# PLA2216.net
KiCad netlist of a schematic drawn in Altium Designer
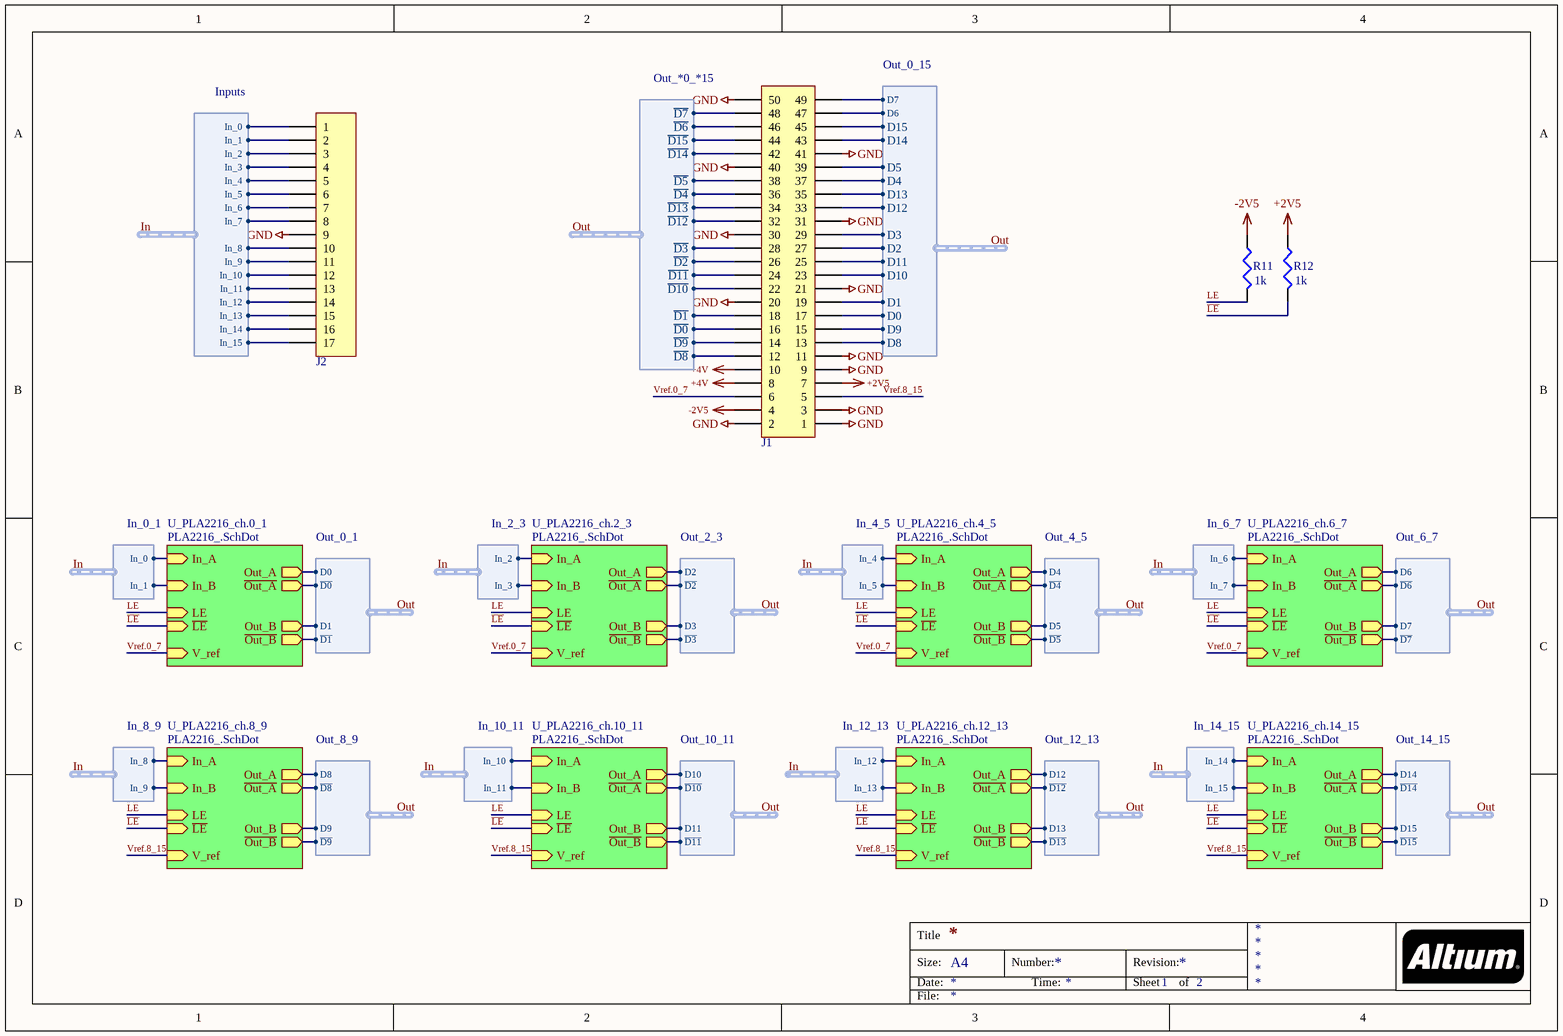
[diagram p0: PLA2216_.SchDoc]

(export (version "E")
  (design (tool "Eeschema 10.0.6"))
  (components
    (comp (ref "J1")
      (value "Header 25X2")
      (footprint "HEADER_25X2")
      (description "50 Position Total Dual Row 2.54 mm Pitch Straight Male Shrouded Box Header")
      (fields
        (field (name "MANUFACTURER") "Sullins")
        (field (name "MANUFACTURER PART NUMBER") "SBH11-PBPC-D25-ST-BK")
      )
      (libsource (lib "PLA2216_sonda") (part "SBH11-PBPC-D25-ST-BK"))
    )
    (comp (ref "J2")
      (value "Header 17X1vf")
      (footprint "HEADER_17")
      (description "Conn Unshrouded Header HDR 17 POS 2.54mm Solder RA Thru-Hole")
      (fields
        (field (name "MANUFACTURER") "Adam Equipment")
        (field (name "MANUFACTURER PART NUMBER") "PH1RB-17-UA")
      )
      (libsource (lib "PLA2216_sonda") (part "PH1RB-17-UA"))
    )
    (comp (ref "R11")
      (value "1k")
      (footprint "R0402")
      (description "Resistor Thick Film 0805 1k Ohm 1% 1/8 Watt ±100ppm °C Surface Mount Paper Tape On Plastic Reel")
      (fields (field (name "TOLERANCE") "1%") (field (name "MANUFACTURER") "Bourns"))
      (libsource (lib "PLA2216_sonda") (part "CR0805-FX-1001ELF"))
    )
    (comp (ref "R12")
      (value "1k")
      (footprint "R0402")
      (description "Resistor Thick Film 0805 1k Ohm 1% 1/8 Watt ±100ppm °C Surface Mount Paper Tape On Plastic Reel")
      (fields (field (name "TOLERANCE") "1%") (field (name "MANUFACTURER") "Bourns"))
      (libsource (lib "PLA2216_sonda") (part "CR0805-FX-1001ELF"))
    )
  )
  (nets
    (net (code "20") (name "+2V5") (class "Default")
      (node (ref "J1") (pin "7") (pinfunction "7_7") (pintype "passive"))
      (node (ref "R12") (pin "1") (pinfunction "1_1") (pintype "passive"))
    )
    (net (code "21") (name "+4V") (class "Default")
      (node (ref "J1") (pin "10") (pinfunction "10_10") (pintype "passive"))
      (node (ref "J1") (pin "8") (pinfunction "8_8") (pintype "passive"))
    )
    (net (code "22") (name "-2V5") (class "Default")
      (node (ref "J1") (pin "4") (pinfunction "4_4") (pintype "passive"))
      (node (ref "R11") (pin "1") (pinfunction "1_1") (pintype "passive"))
    )
    (net (code "48") (name "/LE") (class "Default")
      (node (ref "R11") (pin "2") (pinfunction "2_2") (pintype "passive"))
    )
    (net (code "91") (name "/Vref.0_7") (class "Default")
      (node (ref "J1") (pin "6") (pinfunction "6_6") (pintype "passive"))
    )
    (net (code "92") (name "/Vref.8_15") (class "Default")
      (node (ref "J1") (pin "5") (pinfunction "5_5") (pintype "passive"))
    )
    (net (code "93") (name "/~{LE}") (class "Default")
      (node (ref "R12") (pin "2") (pinfunction "2_2") (pintype "passive"))
    )
    (net (code "94") (name "GND") (class "Default")
      (node (ref "J1") (pin "1") (pinfunction "1_1") (pintype "passive"))
      (node (ref "J1") (pin "11") (pinfunction "11_11") (pintype "passive"))
      (node (ref "J1") (pin "2") (pinfunction "2_2") (pintype "passive"))
      (node (ref "J1") (pin "20") (pinfunction "20_20") (pintype "passive"))
      (node (ref "J1") (pin "21") (pinfunction "21_21") (pintype "passive"))
      (node (ref "J1") (pin "3") (pinfunction "3_3") (pintype "passive"))
      (node (ref "J1") (pin "30") (pinfunction "30_30") (pintype "passive"))
      (node (ref "J1") (pin "31") (pinfunction "31_31") (pintype "passive"))
      (node (ref "J1") (pin "40") (pinfunction "40_40") (pintype "passive"))
      (node (ref "J1") (pin "41") (pinfunction "41_41") (pintype "passive"))
      (node (ref "J1") (pin "50") (pinfunction "50_50") (pintype "passive"))
      (node (ref "J1") (pin "9") (pinfunction "9_9") (pintype "passive"))
      (node (ref "J2") (pin "9") (pinfunction "9_9") (pintype "passive"))
    )
    (net (code "95") (name "unconnected-(J1-Pad12)") (class "Default")
      (node (ref "J1") (pin "12") (pinfunction "12_12") (pintype "passive"))
    )
    (net (code "96") (name "unconnected-(J1-Pad13)") (class "Default")
      (node (ref "J1") (pin "13") (pinfunction "13_13") (pintype "passive"))
    )
    (net (code "97") (name "unconnected-(J1-Pad14)") (class "Default")
      (node (ref "J1") (pin "14") (pinfunction "14_14") (pintype "passive"))
    )
    (net (code "98") (name "unconnected-(J1-Pad15)") (class "Default")
      (node (ref "J1") (pin "15") (pinfunction "15_15") (pintype "passive"))
    )
    (net (code "99") (name "unconnected-(J1-Pad16)") (class "Default")
      (node (ref "J1") (pin "16") (pinfunction "16_16") (pintype "passive"))
    )
    (net (code "100") (name "unconnected-(J1-Pad17)") (class "Default")
      (node (ref "J1") (pin "17") (pinfunction "17_17") (pintype "passive"))
    )
    (net (code "101") (name "unconnected-(J1-Pad18)") (class "Default")
      (node (ref "J1") (pin "18") (pinfunction "18_18") (pintype "passive"))
    )
    (net (code "102") (name "unconnected-(J1-Pad19)") (class "Default")
      (node (ref "J1") (pin "19") (pinfunction "19_19") (pintype "passive"))
    )
    (net (code "103") (name "unconnected-(J1-Pad22)") (class "Default")
      (node (ref "J1") (pin "22") (pinfunction "22_22") (pintype "passive"))
    )
    (net (code "104") (name "unconnected-(J1-Pad23)") (class "Default")
      (node (ref "J1") (pin "23") (pinfunction "23_23") (pintype "passive"))
    )
    (net (code "105") (name "unconnected-(J1-Pad24)") (class "Default")
      (node (ref "J1") (pin "24") (pinfunction "24_24") (pintype "passive"))
    )
    (net (code "106") (name "unconnected-(J1-Pad25)") (class "Default")
      (node (ref "J1") (pin "25") (pinfunction "25_25") (pintype "passive"))
    )
    (net (code "107") (name "unconnected-(J1-Pad26)") (class "Default")
      (node (ref "J1") (pin "26") (pinfunction "26_26") (pintype "passive"))
    )
    (net (code "108") (name "unconnected-(J1-Pad27)") (class "Default")
      (node (ref "J1") (pin "27") (pinfunction "27_27") (pintype "passive"))
    )
    (net (code "109") (name "unconnected-(J1-Pad28)") (class "Default")
      (node (ref "J1") (pin "28") (pinfunction "28_28") (pintype "passive"))
    )
    (net (code "110") (name "unconnected-(J1-Pad29)") (class "Default")
      (node (ref "J1") (pin "29") (pinfunction "29_29") (pintype "passive"))
    )
    (net (code "111") (name "unconnected-(J1-Pad32)") (class "Default")
      (node (ref "J1") (pin "32") (pinfunction "32_32") (pintype "passive"))
    )
    (net (code "112") (name "unconnected-(J1-Pad33)") (class "Default")
      (node (ref "J1") (pin "33") (pinfunction "33_33") (pintype "passive"))
    )
    (net (code "113") (name "unconnected-(J1-Pad34)") (class "Default")
      (node (ref "J1") (pin "34") (pinfunction "34_34") (pintype "passive"))
    )
    (net (code "114") (name "unconnected-(J1-Pad35)") (class "Default")
      (node (ref "J1") (pin "35") (pinfunction "35_35") (pintype "passive"))
    )
    (net (code "115") (name "unconnected-(J1-Pad36)") (class "Default")
      (node (ref "J1") (pin "36") (pinfunction "36_36") (pintype "passive"))
    )
    (net (code "116") (name "unconnected-(J1-Pad37)") (class "Default")
      (node (ref "J1") (pin "37") (pinfunction "37_37") (pintype "passive"))
    )
    (net (code "117") (name "unconnected-(J1-Pad38)") (class "Default")
      (node (ref "J1") (pin "38") (pinfunction "38_38") (pintype "passive"))
    )
    (net (code "118") (name "unconnected-(J1-Pad39)") (class "Default")
      (node (ref "J1") (pin "39") (pinfunction "39_39") (pintype "passive"))
    )
    (net (code "119") (name "unconnected-(J1-Pad42)") (class "Default")
      (node (ref "J1") (pin "42") (pinfunction "42_42") (pintype "passive"))
    )
    (net (code "120") (name "unconnected-(J1-Pad43)") (class "Default")
      (node (ref "J1") (pin "43") (pinfunction "43_43") (pintype "passive"))
    )
    (net (code "121") (name "unconnected-(J1-Pad44)") (class "Default")
      (node (ref "J1") (pin "44") (pinfunction "44_44") (pintype "passive"))
    )
    (net (code "122") (name "unconnected-(J1-Pad45)") (class "Default")
      (node (ref "J1") (pin "45") (pinfunction "45_45") (pintype "passive"))
    )
    (net (code "123") (name "unconnected-(J1-Pad46)") (class "Default")
      (node (ref "J1") (pin "46") (pinfunction "46_46") (pintype "passive"))
    )
    (net (code "124") (name "unconnected-(J1-Pad47)") (class "Default")
      (node (ref "J1") (pin "47") (pinfunction "47_47") (pintype "passive"))
    )
    (net (code "125") (name "unconnected-(J1-Pad48)") (class "Default")
      (node (ref "J1") (pin "48") (pinfunction "48_48") (pintype "passive"))
    )
    (net (code "126") (name "unconnected-(J1-Pad49)") (class "Default")
      (node (ref "J1") (pin "49") (pinfunction "49_49") (pintype "passive"))
    )
    (net (code "127") (name "unconnected-(J2-Pad1)") (class "Default")
      (node (ref "J2") (pin "1") (pinfunction "1_1") (pintype "passive"))
    )
    (net (code "128") (name "unconnected-(J2-Pad2)") (class "Default")
      (node (ref "J2") (pin "2") (pinfunction "2_2") (pintype "passive"))
    )
    (net (code "129") (name "unconnected-(J2-Pad3)") (class "Default")
      (node (ref "J2") (pin "3") (pinfunction "3_3") (pintype "passive"))
    )
    (net (code "130") (name "unconnected-(J2-Pad4)") (class "Default")
      (node (ref "J2") (pin "4") (pinfunction "4_4") (pintype "passive"))
    )
    (net (code "131") (name "unconnected-(J2-Pad5)") (class "Default")
      (node (ref "J2") (pin "5") (pinfunction "5_5") (pintype "passive"))
    )
    (net (code "132") (name "unconnected-(J2-Pad6)") (class "Default")
      (node (ref "J2") (pin "6") (pinfunction "6_6") (pintype "passive"))
    )
    (net (code "133") (name "unconnected-(J2-Pad7)") (class "Default")
      (node (ref "J2") (pin "7") (pinfunction "7_7") (pintype "passive"))
    )
    (net (code "134") (name "unconnected-(J2-Pad8)") (class "Default")
      (node (ref "J2") (pin "8") (pinfunction "8_8") (pintype "passive"))
    )
    (net (code "135") (name "unconnected-(J2-Pad10)") (class "Default")
      (node (ref "J2") (pin "10") (pinfunction "10_10") (pintype "passive"))
    )
    (net (code "136") (name "unconnected-(J2-Pad11)") (class "Default")
      (node (ref "J2") (pin "11") (pinfunction "11_11") (pintype "passive"))
    )
    (net (code "137") (name "unconnected-(J2-Pad12)") (class "Default")
      (node (ref "J2") (pin "12") (pinfunction "12_12") (pintype "passive"))
    )
    (net (code "138") (name "unconnected-(J2-Pad13)") (class "Default")
      (node (ref "J2") (pin "13") (pinfunction "13_13") (pintype "passive"))
    )
    (net (code "139") (name "unconnected-(J2-Pad14)") (class "Default")
      (node (ref "J2") (pin "14") (pinfunction "14_14") (pintype "passive"))
    )
    (net (code "140") (name "unconnected-(J2-Pad15)") (class "Default")
      (node (ref "J2") (pin "15") (pinfunction "15_15") (pintype "passive"))
    )
    (net (code "141") (name "unconnected-(J2-Pad16)") (class "Default")
      (node (ref "J2") (pin "16") (pinfunction "16_16") (pintype "passive"))
    )
    (net (code "142") (name "unconnected-(J2-Pad17)") (class "Default")
      (node (ref "J2") (pin "17") (pinfunction "17_17") (pintype "passive"))
    )
  )
)
